# M204X.net
KiCad netlist of a schematic drawn in EAGLE
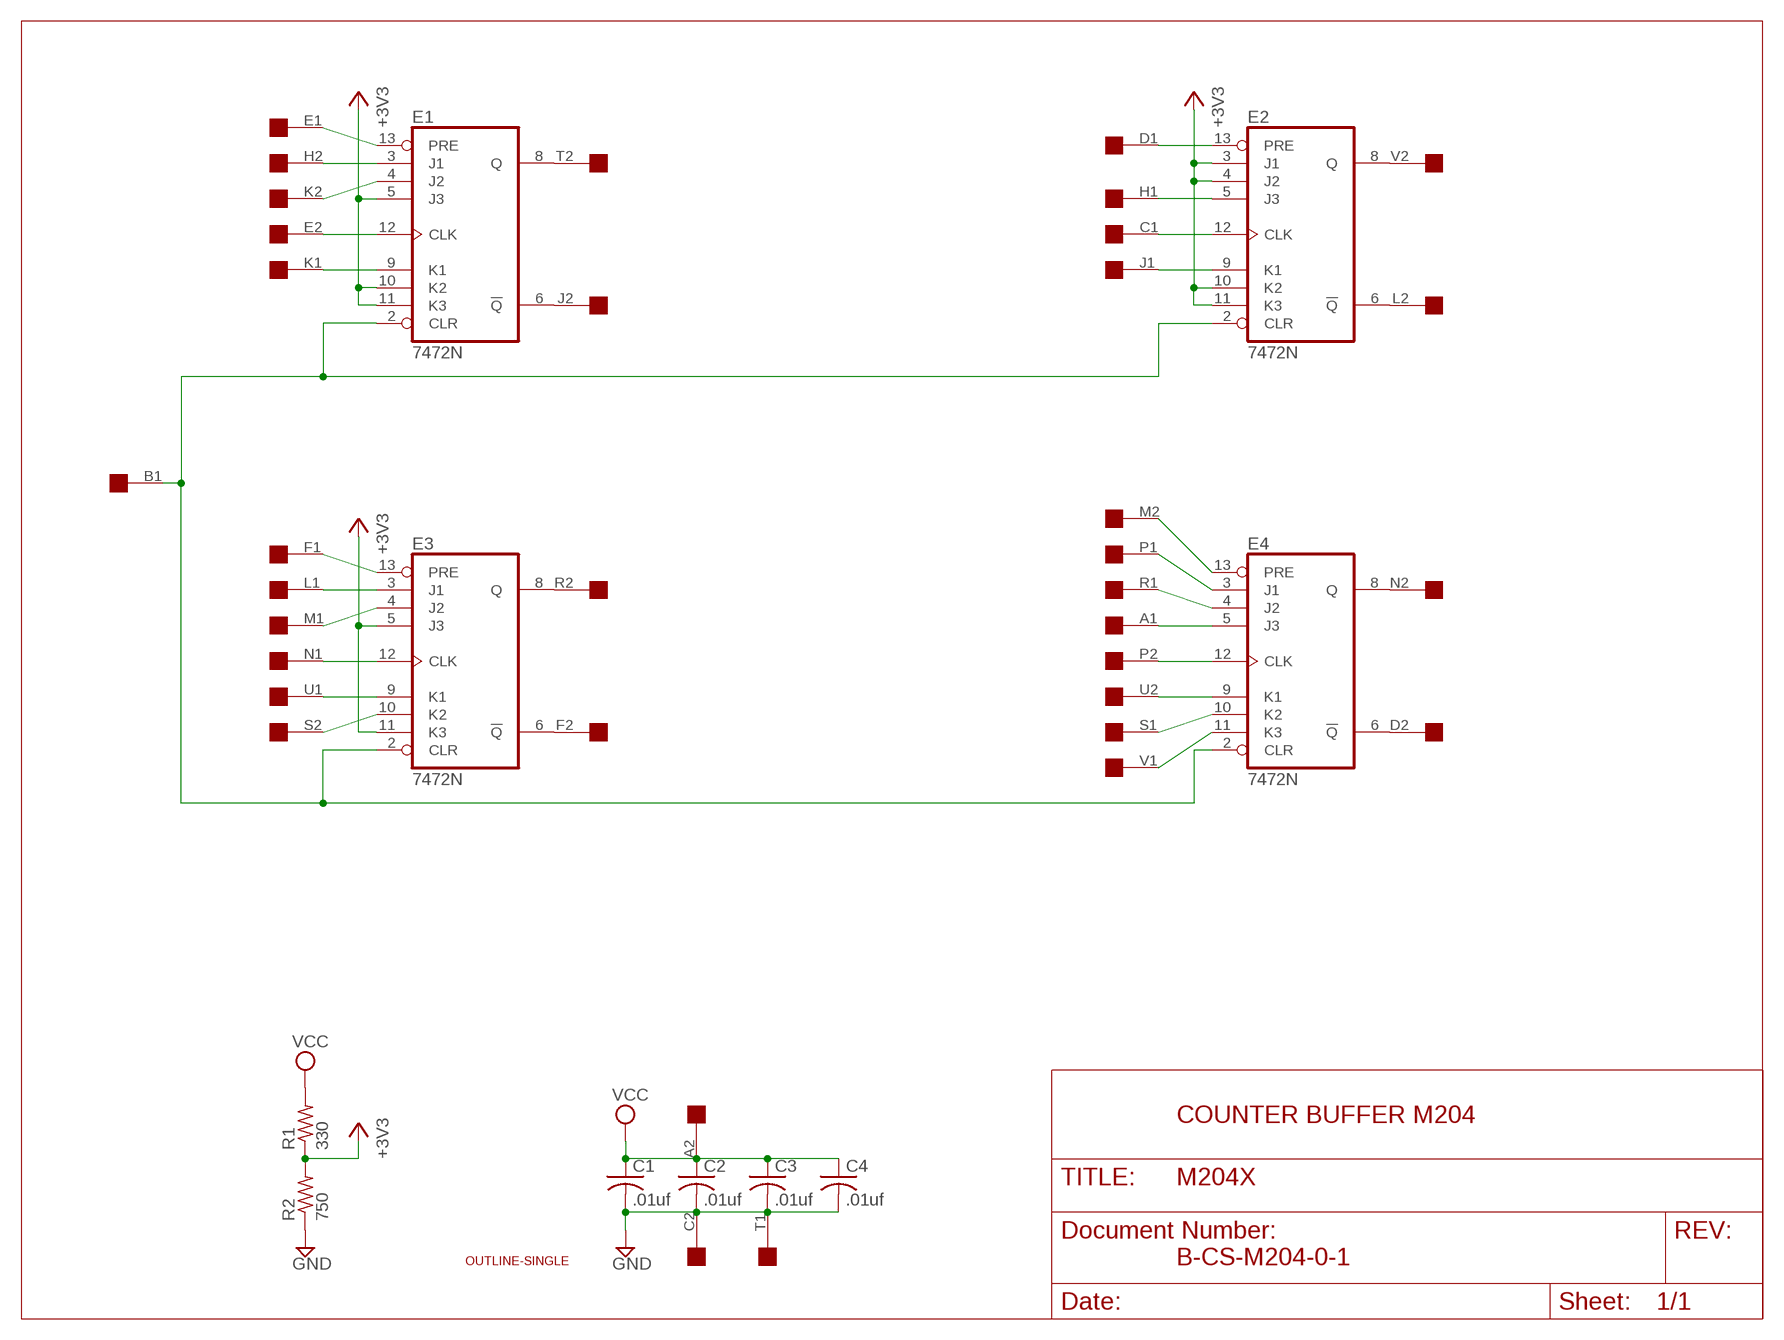
[diagram p0: schematic, sheet 1]

(export (version "E")
  (design (tool "Eeschema 10.0.6"))
  (components
    (comp (ref "C1")
      (value ".01uf")
      (footprint "eagle-import:C050-025X075")
      (libsource (lib "eagle-import") (part "C-US050-025X075"))
    )
    (comp (ref "C2")
      (value ".01uf")
      (footprint "eagle-import:C050-025X075")
      (libsource (lib "eagle-import") (part "C-US050-025X075"))
    )
    (comp (ref "C3")
      (value ".01uf")
      (footprint "eagle-import:C050-025X075")
      (libsource (lib "eagle-import") (part "C-US050-025X075"))
    )
    (comp (ref "C4")
      (value ".01uf")
      (footprint "eagle-import:C050-025X075")
      (libsource (lib "eagle-import") (part "C-US050-025X075"))
    )
    (comp (ref "E1")
      (value "7472N")
      (footprint "eagle-import:DIL14")
      (libsource (lib "eagle-import") (part "7472N"))
    )
    (comp (ref "E2")
      (value "7472N")
      (footprint "eagle-import:DIL14")
      (libsource (lib "eagle-import") (part "7472N"))
    )
    (comp (ref "E3")
      (value "7472N")
      (footprint "eagle-import:DIL14")
      (libsource (lib "eagle-import") (part "7472N"))
    )
    (comp (ref "E4")
      (value "7472N")
      (footprint "eagle-import:DIL14")
      (libsource (lib "eagle-import") (part "7472N"))
    )
    (comp (ref "R1")
      (value "330")
      (footprint "eagle-import:0207_10")
      (libsource (lib "eagle-import") (part "R-US_0207/10"))
    )
    (comp (ref "R2")
      (value "750")
      (footprint "eagle-import:0207_10")
      (libsource (lib "eagle-import") (part "R-US_0207/10"))
    )
    (comp (ref "U$1")
      (value "OUTLINE-SINGLE")
      (footprint "eagle-import:SINGLE")
      (libsource (lib "eagle-import") (part "OUTLINE-SINGLE"))
    )
    (comp (ref "U$2")
      (value "EDGE-2CONNECTOR")
      (footprint "eagle-import:EDGE-CON2")
      (libsource (lib "eagle-import") (part "EDGE-2CONNECTOR"))
    )
  )
  (nets
    (net (code "1") (name "+3V3") (class "Default")
      (node (ref "E1") (pin "10") (pinfunction "K2_10") (pintype "input"))
      (node (ref "E1") (pin "11") (pinfunction "K3_11") (pintype "input"))
      (node (ref "E1") (pin "5") (pinfunction "J3_5") (pintype "input"))
      (node (ref "E2") (pin "10") (pinfunction "K2_10") (pintype "input"))
      (node (ref "E2") (pin "11") (pinfunction "K3_11") (pintype "input"))
      (node (ref "E2") (pin "3") (pinfunction "J1_3") (pintype "input"))
      (node (ref "E2") (pin "4") (pinfunction "J2_4") (pintype "input"))
      (node (ref "E3") (pin "11") (pinfunction "K3_11") (pintype "input"))
      (node (ref "E3") (pin "5") (pinfunction "J3_5") (pintype "input"))
      (node (ref "R1") (pin "1") (pinfunction "1_1") (pintype "passive"))
      (node (ref "R2") (pin "2") (pinfunction "2_2") (pintype "passive"))
    )
    (net (code "2") (name "GND") (class "Default")
      (node (ref "C1") (pin "2") (pinfunction "2_2") (pintype "passive"))
      (node (ref "C2") (pin "2") (pinfunction "2_2") (pintype "passive"))
      (node (ref "C3") (pin "2") (pinfunction "2_2") (pintype "passive"))
      (node (ref "C4") (pin "2") (pinfunction "2_2") (pintype "passive"))
      (node (ref "R2") (pin "1") (pinfunction "1_1") (pintype "passive"))
      (node (ref "U$2") (pin "C2") (pinfunction "1_C2") (pintype "bidirectional"))
      (node (ref "U$2") (pin "T1") (pinfunction "1_T1") (pintype "bidirectional"))
    )
    (net (code "3") (name "Net-(E1A-CLK)") (class "Default")
      (node (ref "E1") (pin "12") (pinfunction "CLK_12") (pintype "input"))
      (node (ref "U$2") (pin "E2") (pinfunction "1_E2") (pintype "bidirectional"))
    )
    (net (code "4") (name "Net-(E1A-CLR)") (class "Default")
      (node (ref "E1") (pin "2") (pinfunction "CLR_2") (pintype "input"))
      (node (ref "E2") (pin "2") (pinfunction "CLR_2") (pintype "input"))
      (node (ref "E3") (pin "2") (pinfunction "CLR_2") (pintype "input"))
      (node (ref "E4") (pin "2") (pinfunction "CLR_2") (pintype "input"))
      (node (ref "U$2") (pin "B1") (pinfunction "1_B1") (pintype "bidirectional"))
    )
    (net (code "5") (name "Net-(E1A-J1)") (class "Default")
      (node (ref "E1") (pin "3") (pinfunction "J1_3") (pintype "input"))
      (node (ref "U$2") (pin "H2") (pinfunction "1_H2") (pintype "bidirectional"))
    )
    (net (code "6") (name "Net-(E1A-J2)") (class "Default")
      (node (ref "E1") (pin "4") (pinfunction "J2_4") (pintype "input"))
      (node (ref "U$2") (pin "K2") (pinfunction "1_K2") (pintype "bidirectional"))
    )
    (net (code "7") (name "Net-(E1A-K1)") (class "Default")
      (node (ref "E1") (pin "9") (pinfunction "K1_9") (pintype "input"))
      (node (ref "U$2") (pin "K1") (pinfunction "1_K1") (pintype "bidirectional"))
    )
    (net (code "8") (name "Net-(E1A-PRE)") (class "Default")
      (node (ref "E1") (pin "13") (pinfunction "PRE_13") (pintype "input"))
      (node (ref "U$2") (pin "E1") (pinfunction "1_E1") (pintype "bidirectional"))
    )
    (net (code "9") (name "Net-(E1A-Q)") (class "Default")
      (node (ref "E1") (pin "8") (pinfunction "Q_8") (pintype "output"))
      (node (ref "U$2") (pin "T2") (pinfunction "1_T2") (pintype "bidirectional"))
    )
    (net (code "10") (name "Net-(E1A-~{Q})") (class "Default")
      (node (ref "E1") (pin "6") (pinfunction "~{Q}_6") (pintype "output"))
      (node (ref "U$2") (pin "J2") (pinfunction "1_J2") (pintype "bidirectional"))
    )
    (net (code "11") (name "Net-(E2A-CLK)") (class "Default")
      (node (ref "E2") (pin "12") (pinfunction "CLK_12") (pintype "input"))
      (node (ref "U$2") (pin "C1") (pinfunction "1_C1") (pintype "bidirectional"))
    )
    (net (code "12") (name "Net-(E2A-J3)") (class "Default")
      (node (ref "E2") (pin "5") (pinfunction "J3_5") (pintype "input"))
      (node (ref "U$2") (pin "H1") (pinfunction "1_H1") (pintype "bidirectional"))
    )
    (net (code "13") (name "Net-(E2A-K1)") (class "Default")
      (node (ref "E2") (pin "9") (pinfunction "K1_9") (pintype "input"))
      (node (ref "U$2") (pin "J1") (pinfunction "1_J1") (pintype "bidirectional"))
    )
    (net (code "14") (name "Net-(E2A-PRE)") (class "Default")
      (node (ref "E2") (pin "13") (pinfunction "PRE_13") (pintype "input"))
      (node (ref "U$2") (pin "D1") (pinfunction "1_D1") (pintype "bidirectional"))
    )
    (net (code "15") (name "Net-(E2A-Q)") (class "Default")
      (node (ref "E2") (pin "8") (pinfunction "Q_8") (pintype "output"))
      (node (ref "U$2") (pin "V2") (pinfunction "1_V2") (pintype "bidirectional"))
    )
    (net (code "16") (name "Net-(E2A-~{Q})") (class "Default")
      (node (ref "E2") (pin "6") (pinfunction "~{Q}_6") (pintype "output"))
      (node (ref "U$2") (pin "L2") (pinfunction "1_L2") (pintype "bidirectional"))
    )
    (net (code "17") (name "Net-(E3A-CLK)") (class "Default")
      (node (ref "E3") (pin "12") (pinfunction "CLK_12") (pintype "input"))
      (node (ref "U$2") (pin "N1") (pinfunction "1_N1") (pintype "bidirectional"))
    )
    (net (code "18") (name "Net-(E3A-J1)") (class "Default")
      (node (ref "E3") (pin "3") (pinfunction "J1_3") (pintype "input"))
      (node (ref "U$2") (pin "L1") (pinfunction "1_L1") (pintype "bidirectional"))
    )
    (net (code "19") (name "Net-(E3A-J2)") (class "Default")
      (node (ref "E3") (pin "4") (pinfunction "J2_4") (pintype "input"))
      (node (ref "U$2") (pin "M1") (pinfunction "1_M1") (pintype "bidirectional"))
    )
    (net (code "20") (name "Net-(E3A-K1)") (class "Default")
      (node (ref "E3") (pin "9") (pinfunction "K1_9") (pintype "input"))
      (node (ref "U$2") (pin "U1") (pinfunction "1_U1") (pintype "bidirectional"))
    )
    (net (code "21") (name "Net-(E3A-K2)") (class "Default")
      (node (ref "E3") (pin "10") (pinfunction "K2_10") (pintype "input"))
      (node (ref "U$2") (pin "S2") (pinfunction "1_S2") (pintype "bidirectional"))
    )
    (net (code "22") (name "Net-(E3A-PRE)") (class "Default")
      (node (ref "E3") (pin "13") (pinfunction "PRE_13") (pintype "input"))
      (node (ref "U$2") (pin "F1") (pinfunction "1_F1") (pintype "bidirectional"))
    )
    (net (code "23") (name "Net-(E3A-Q)") (class "Default")
      (node (ref "E3") (pin "8") (pinfunction "Q_8") (pintype "output"))
      (node (ref "U$2") (pin "R2") (pinfunction "1_R2") (pintype "bidirectional"))
    )
    (net (code "24") (name "Net-(E3A-~{Q})") (class "Default")
      (node (ref "E3") (pin "6") (pinfunction "~{Q}_6") (pintype "output"))
      (node (ref "U$2") (pin "F2") (pinfunction "1_F2") (pintype "bidirectional"))
    )
    (net (code "25") (name "Net-(E4A-CLK)") (class "Default")
      (node (ref "E4") (pin "12") (pinfunction "CLK_12") (pintype "input"))
      (node (ref "U$2") (pin "P2") (pinfunction "1_P2") (pintype "bidirectional"))
    )
    (net (code "26") (name "Net-(E4A-J1)") (class "Default")
      (node (ref "E4") (pin "3") (pinfunction "J1_3") (pintype "input"))
      (node (ref "U$2") (pin "P1") (pinfunction "1_P1") (pintype "bidirectional"))
    )
    (net (code "27") (name "Net-(E4A-J2)") (class "Default")
      (node (ref "E4") (pin "4") (pinfunction "J2_4") (pintype "input"))
      (node (ref "U$2") (pin "R1") (pinfunction "1_R1") (pintype "bidirectional"))
    )
    (net (code "28") (name "Net-(E4A-J3)") (class "Default")
      (node (ref "E4") (pin "5") (pinfunction "J3_5") (pintype "input"))
      (node (ref "U$2") (pin "A1") (pinfunction "1_A1") (pintype "bidirectional"))
    )
    (net (code "29") (name "Net-(E4A-K1)") (class "Default")
      (node (ref "E4") (pin "9") (pinfunction "K1_9") (pintype "input"))
      (node (ref "U$2") (pin "U2") (pinfunction "1_U2") (pintype "bidirectional"))
    )
    (net (code "30") (name "Net-(E4A-K2)") (class "Default")
      (node (ref "E4") (pin "10") (pinfunction "K2_10") (pintype "input"))
      (node (ref "U$2") (pin "S1") (pinfunction "1_S1") (pintype "bidirectional"))
    )
    (net (code "31") (name "Net-(E4A-K3)") (class "Default")
      (node (ref "E4") (pin "11") (pinfunction "K3_11") (pintype "input"))
      (node (ref "U$2") (pin "V1") (pinfunction "1_V1") (pintype "bidirectional"))
    )
    (net (code "32") (name "Net-(E4A-PRE)") (class "Default")
      (node (ref "E4") (pin "13") (pinfunction "PRE_13") (pintype "input"))
      (node (ref "U$2") (pin "M2") (pinfunction "1_M2") (pintype "bidirectional"))
    )
    (net (code "33") (name "Net-(E4A-Q)") (class "Default")
      (node (ref "E4") (pin "8") (pinfunction "Q_8") (pintype "output"))
      (node (ref "U$2") (pin "N2") (pinfunction "1_N2") (pintype "bidirectional"))
    )
    (net (code "34") (name "Net-(E4A-~{Q})") (class "Default")
      (node (ref "E4") (pin "6") (pinfunction "~{Q}_6") (pintype "output"))
      (node (ref "U$2") (pin "D2") (pinfunction "1_D2") (pintype "bidirectional"))
    )
    (net (code "35") (name "VCC") (class "Default")
      (node (ref "C1") (pin "1") (pinfunction "1_1") (pintype "passive"))
      (node (ref "C2") (pin "1") (pinfunction "1_1") (pintype "passive"))
      (node (ref "C3") (pin "1") (pinfunction "1_1") (pintype "passive"))
      (node (ref "C4") (pin "1") (pinfunction "1_1") (pintype "passive"))
      (node (ref "R1") (pin "2") (pinfunction "2_2") (pintype "passive"))
      (node (ref "U$2") (pin "A2") (pinfunction "1_A2") (pintype "bidirectional"))
    )
  )
)
